# H09R9x.net
KiCad netlist of a schematic drawn in EAGLE
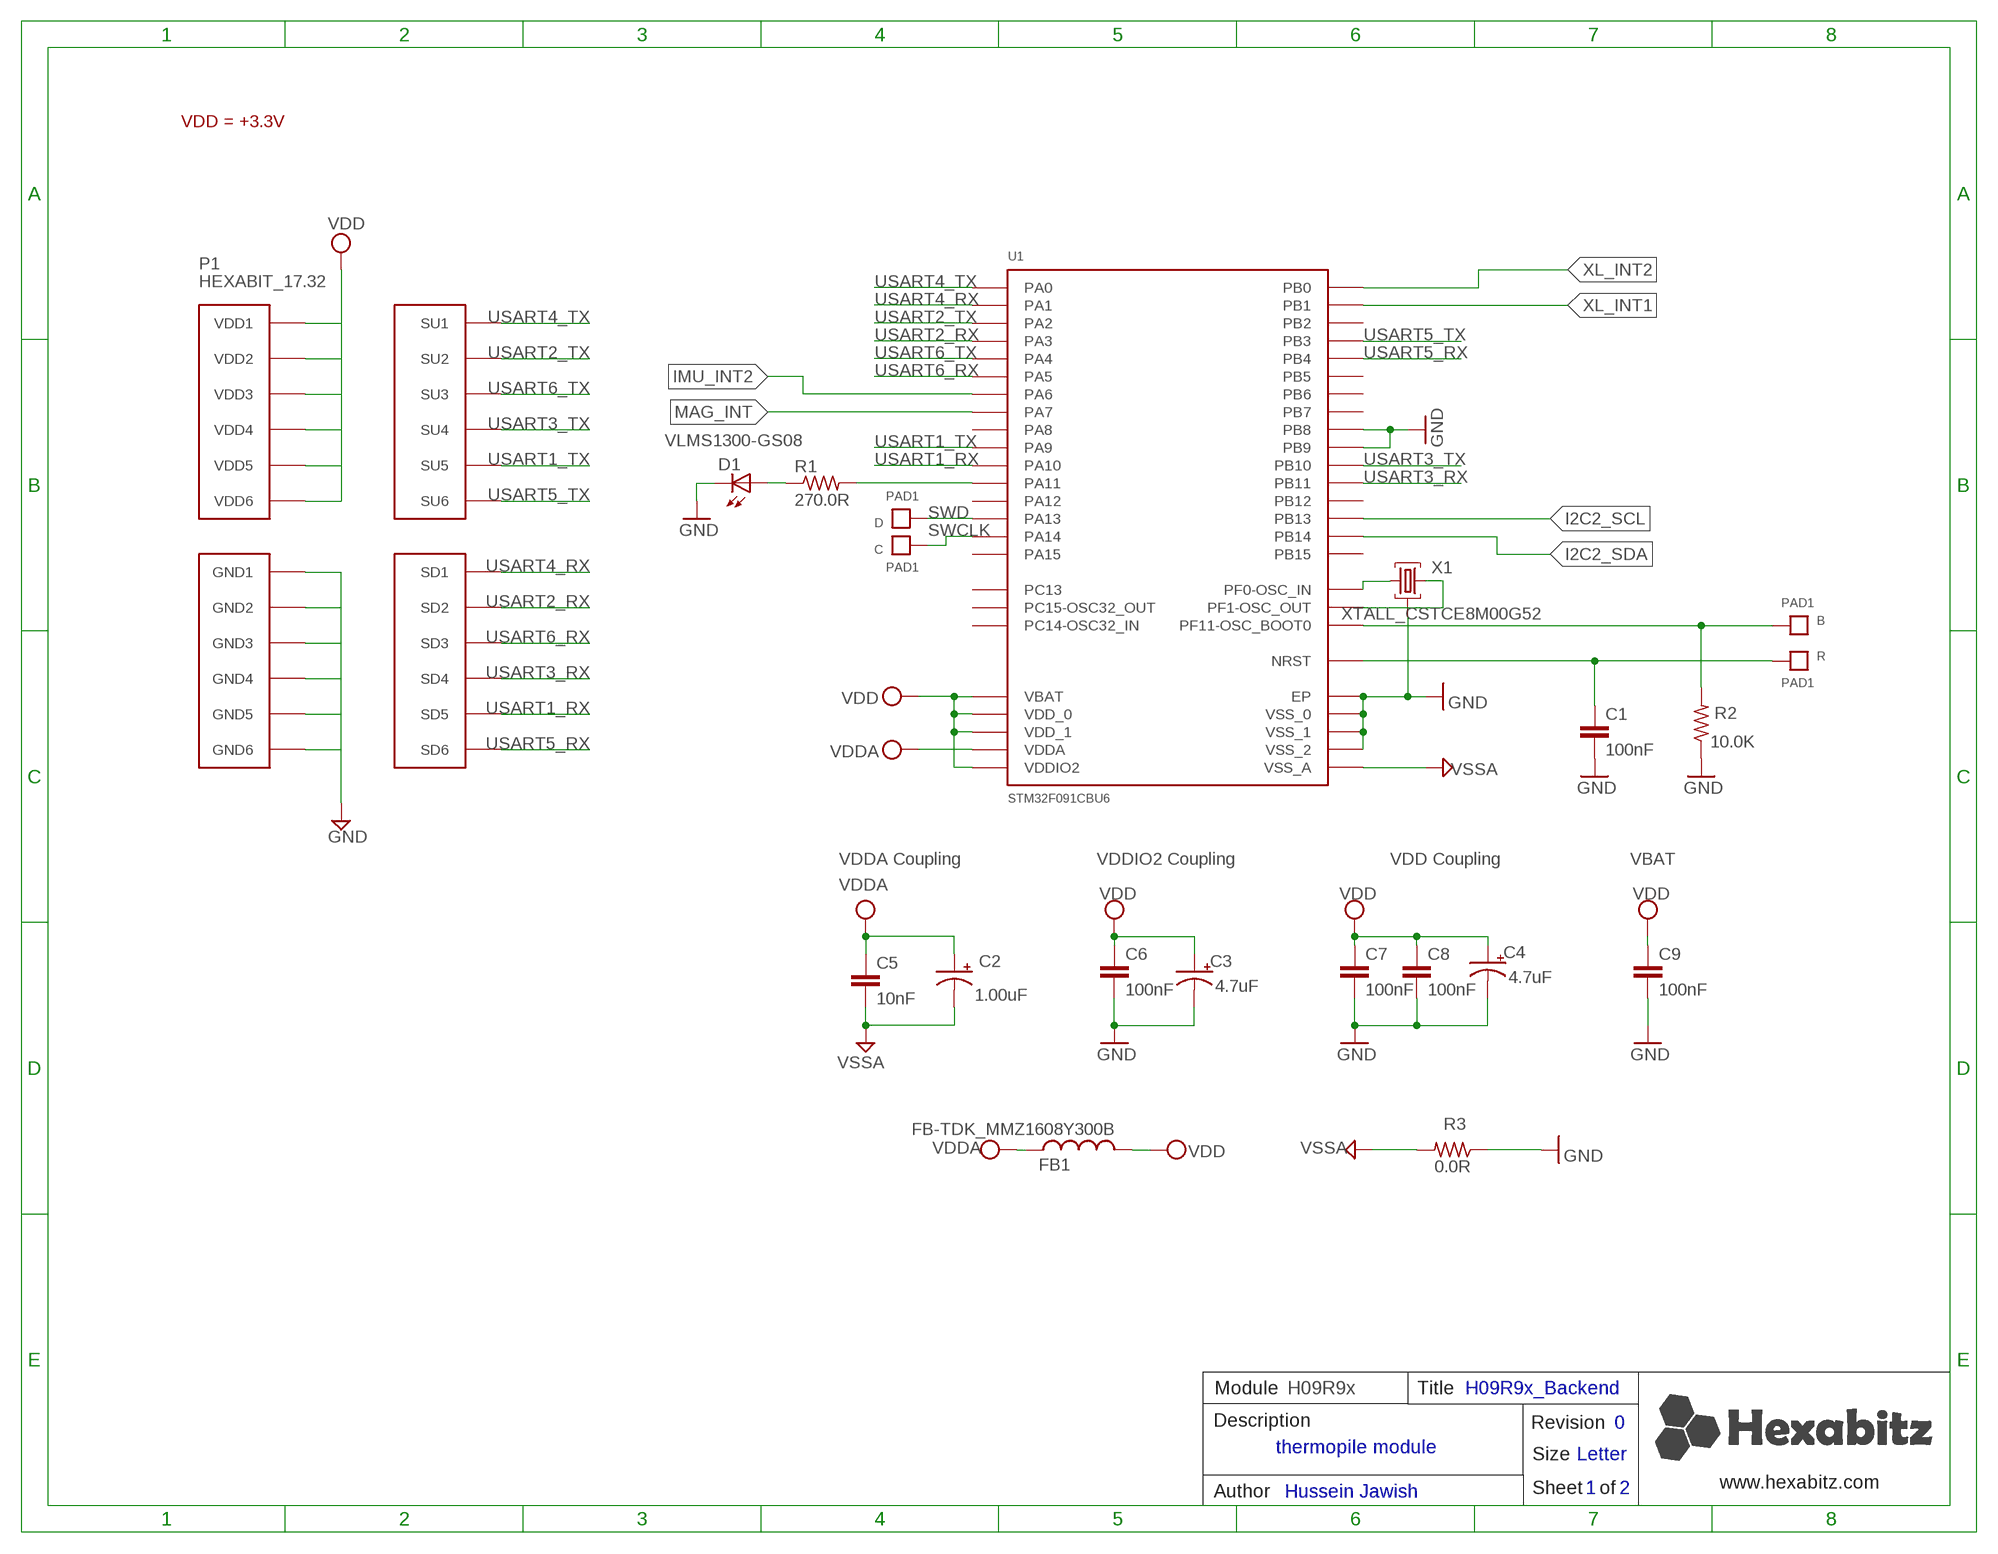
[diagram p0: schematic, sheet 1]
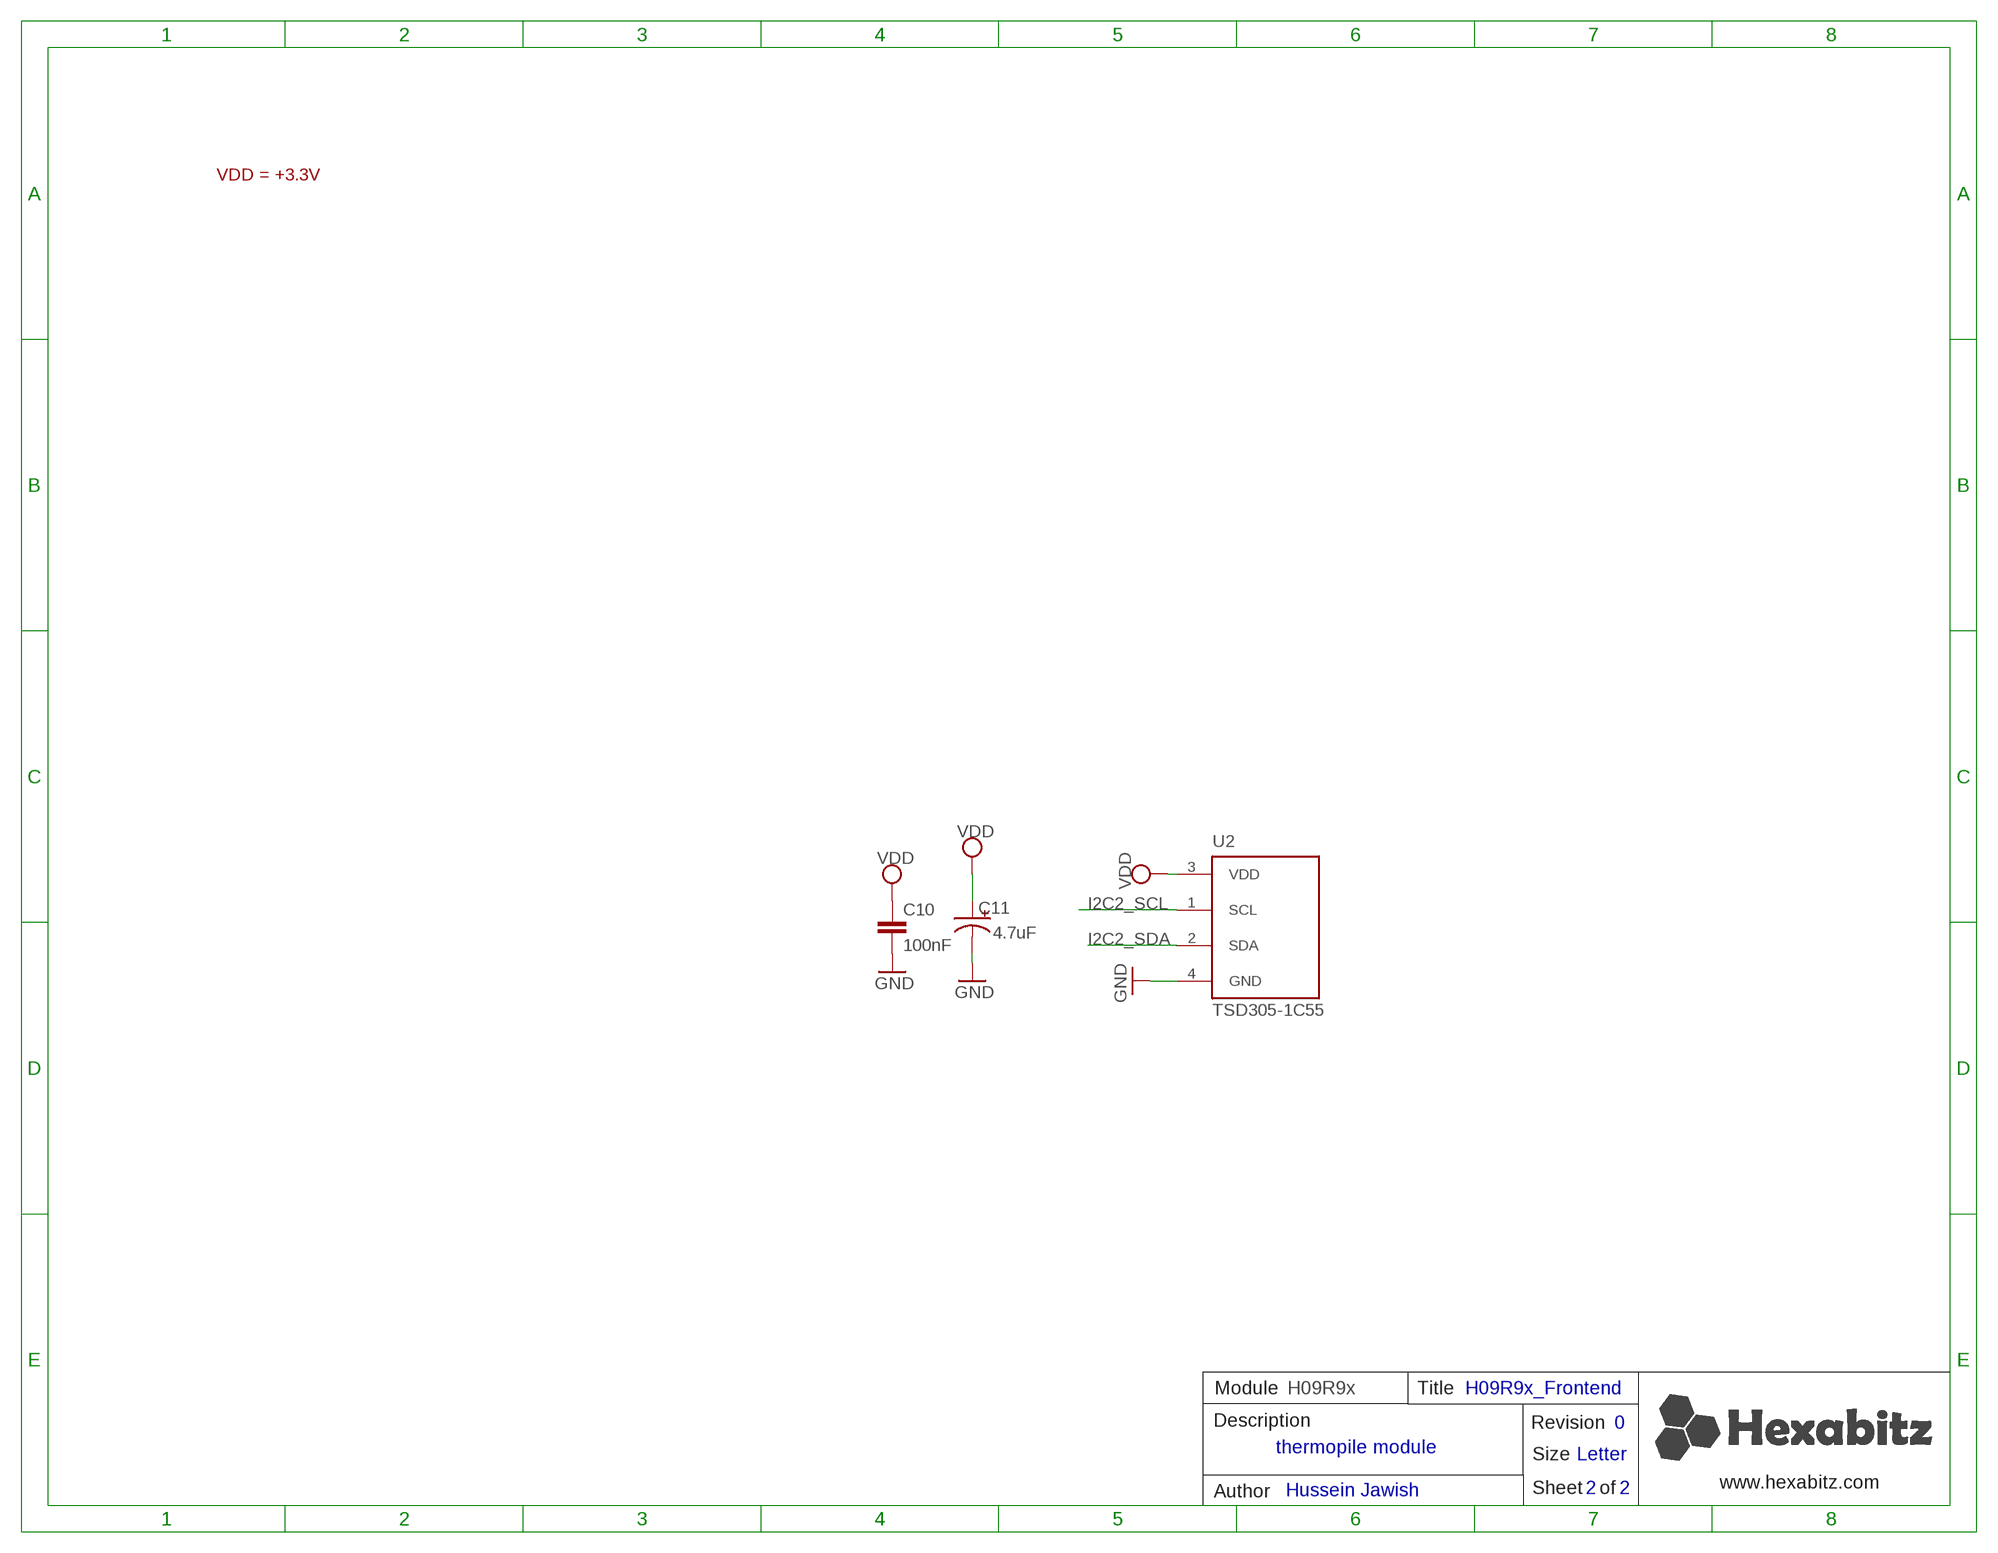
[diagram p1: schematic, sheet 2]

(export (version "E")
  (design (tool "Eeschema 10.0.6"))
  (components
    (comp (ref "B")
      (value "PAD1")
      (footprint "eagle-import:PAD1")
      (libsource (lib "eagle-import") (part "PAD1"))
    )
    (comp (ref "C")
      (value "PAD1")
      (footprint "eagle-import:PAD1")
      (libsource (lib "eagle-import") (part "PAD1"))
    )
    (comp (ref "C1")
      (value "100nF")
      (footprint "eagle-import:C-0603")
      (fields
        (field (name "CAPACITANCE") "100nF")
        (field (name "MFN") "AVX")
        (field (name "MPN") "0603YC104K4T2A")
        (field (name "OCTOPART_URL") "https://octopart.com/0603yc104k4t2a-avx+interconnect+%2F+elco-8120651")
        (field (name "TOLERANCE") "10%")
        (field (name "VOLTAGE_RATING") "16.0 V")
      )
      (libsource (lib "eagle-import") (part "C-0603"))
    )
    (comp (ref "C2")
      (value "1.00uF")
      (footprint "eagle-import:C-0805-POL")
      (fields
        (field (name "CAPACITANCE") "1.00uF")
        (field (name "MFN") "AVX")
        (field (name "MPN") "TAJR105M016RNJ")
        (field (name "OCTOPART_URL") "http://octopart.com/tajr105m016rnj-avx-1188552")
        (field (name "TOLERANCE") "10%")
        (field (name "VOLTAGE_RATING") "16.0 V")
      )
      (libsource (lib "eagle-import") (part "C-0805-POL"))
    )
    (comp (ref "C3")
      (value "4.7uF")
      (footprint "eagle-import:C-0805-POL")
      (fields
        (field (name "CAPACITANCE") "4.7uF")
        (field (name "MFN") "Panasonic")
        (field (name "MPN") "10TPU4R7MSI")
        (field (name "OCTOPART_URL") "https://octopart.com/10tpu4r7msi-panasonic-29487748")
        (field (name "TOLERANCE") "20%")
        (field (name "VOLTAGE_RATING") "10.0 V")
      )
      (libsource (lib "eagle-import") (part "C-0805-POL"))
    )
    (comp (ref "C4")
      (value "4.7uF")
      (footprint "eagle-import:C-0805-POL")
      (fields
        (field (name "CAPACITANCE") "4.7uF")
        (field (name "MFN") "Panasonic")
        (field (name "MPN") "10TPU4R7MSI")
        (field (name "OCTOPART_URL") "https://octopart.com/10tpu4r7msi-panasonic-29487748")
        (field (name "TOLERANCE") "10%")
        (field (name "VOLTAGE_RATING") "10 V")
      )
      (libsource (lib "eagle-import") (part "C-0805-POL"))
    )
    (comp (ref "C5")
      (value "10nF")
      (footprint "eagle-import:C-0603")
      (fields
        (field (name "CAPACITANCE") "10nF")
        (field (name "MFN") "AVX")
        (field (name "MPN") "0603YC103KAT4A")
        (field (name "OCTOPART_URL") "https://octopart.com/0603yc103kat4a-avx+interconnect+%2F+elco-2550362")
        (field (name "TOLERANCE") "10%")
        (field (name "VOLTAGE_RATING") "16.0 V")
      )
      (libsource (lib "eagle-import") (part "C-0603"))
    )
    (comp (ref "C6")
      (value "100nF")
      (footprint "eagle-import:C-0603")
      (fields
        (field (name "CAPACITANCE") "100nF")
        (field (name "MFN") "AVX")
        (field (name "MPN") "0603YC104K4T2A")
        (field (name "OCTOPART_URL") "https://octopart.com/0603yc104k4t2a-avx+interconnect+%2F+elco-8120651")
        (field (name "TOLERANCE") "10%")
        (field (name "VOLTAGE_RATING") "16.0 V")
      )
      (libsource (lib "eagle-import") (part "C-0603"))
    )
    (comp (ref "C7")
      (value "100nF")
      (footprint "eagle-import:C-0603")
      (fields
        (field (name "CAPACITANCE") "100nF")
        (field (name "MFN") "AVX")
        (field (name "MPN") "0603YC104K4T2A")
        (field (name "OCTOPART_URL") "https://octopart.com/0603yc104k4t2a-avx+interconnect+%2F+elco-8120651")
        (field (name "TOLERANCE") "10%")
        (field (name "VOLTAGE_RATING") "16.0 V")
      )
      (libsource (lib "eagle-import") (part "C-0603"))
    )
    (comp (ref "C8")
      (value "100nF")
      (footprint "eagle-import:C-0603")
      (fields
        (field (name "CAPACITANCE") "100nF")
        (field (name "MFN") "AVX")
        (field (name "MPN") "0603YC104K4T2A")
        (field (name "OCTOPART_URL") "https://octopart.com/0603yc104k4t2a-avx+interconnect+%2F+elco-8120651")
        (field (name "TOLERANCE") "10%")
        (field (name "VOLTAGE_RATING") "16.0 V")
      )
      (libsource (lib "eagle-import") (part "C-0603"))
    )
    (comp (ref "C9")
      (value "100nF")
      (footprint "eagle-import:C-0603")
      (fields
        (field (name "CAPACITANCE") "100nF")
        (field (name "MFN") "AVX")
        (field (name "MPN") "0603YC104K4T2A")
        (field (name "OCTOPART_URL") "https://octopart.com/0603yc104k4t2a-avx+interconnect+%2F+elco-8120651")
        (field (name "TOLERANCE") "16.0 V")
        (field (name "VOLTAGE_RATING") "10%")
      )
      (libsource (lib "eagle-import") (part "C-0603"))
    )
    (comp (ref "D")
      (value "PAD1")
      (footprint "eagle-import:PAD1")
      (libsource (lib "eagle-import") (part "PAD1"))
    )
    (comp (ref "D1")
      (value "VLMS1300-GS08")
      (footprint "eagle-import:VLMS1300-GS08")
      (fields
        (field (name "MFN") "Vishay")
        (field (name "MPN") "VLMS1300-GS08")
        (field (name "OCTOPART_URL") "https://octopart.com/vlms1300-gs08-vishay-21709201?r=sp&s=_gcP4_q8T1SC6PJQPTQ9yA")
      )
      (libsource (lib "eagle-import") (part "VLMS1300-GS08"))
    )
    (comp (ref "FB1")
      (value "FB-TDK_MMZ1608Y300B")
      (footprint "eagle-import:FB-TDK_MMZ1608Y300B")
      (fields
        (field (name "MFN") "TDK ")
        (field (name "MPN") "MMZ1608Y300B")
        (field (name "OCTOPART_URL") "https://octopart.com/mmz1608y300b-tdk-368280?r=sp&s=cd9_2ZEqQ9q9UNBuQgHAiA")
      )
      (libsource (lib "eagle-import") (part "FB-TDK_MMZ1608Y300B"))
    )
    (comp (ref "P1")
      (value "HEXABIT_17.32")
      (footprint "eagle-import:HEXABIT_17.32")
      (libsource (lib "eagle-import") (part "HEXABIT_?17.32"))
    )
    (comp (ref "R")
      (value "PAD1")
      (footprint "eagle-import:PAD1")
      (libsource (lib "eagle-import") (part "PAD1"))
    )
    (comp (ref "R1")
      (value "270.0R")
      (footprint "eagle-import:R-0603")
      (fields
        (field (name "MFN") "Panasonic")
        (field (name "MPN") "ERJ-3GEYJ271V")
        (field (name "OCTOPART_URL") "https://octopart.com/erj-3geyj271v-panasonic-55560546")
        (field (name "RESISTANCE") "270.0 Ohm")
        (field (name "TOLERANCE") "5%")
      )
      (libsource (lib "eagle-import") (part "R-0603"))
    )
    (comp (ref "R2")
      (value "10.0K")
      (footprint "eagle-import:R-0603")
      (fields
        (field (name "MFN") "Vishay")
        (field (name "MPN") "CRCW060310K0JNEB")
        (field (name "OCTOPART_URL") "https://octopart.com/crcw060310k0jneb-vishay-46603269")
        (field (name "RESISTANCE") "10.0K Ohm")
        (field (name "TOLERANCE") "5%")
      )
      (libsource (lib "eagle-import") (part "R-0603"))
    )
    (comp (ref "R3")
      (value "0.0R")
      (footprint "eagle-import:R-0603")
      (fields
        (field (name "MFN") "Vishay")
        (field (name "MPN") "CRCW06030000Z0EAHP")
        (field (name "OCTOPART_URL") "https://octopart.com/crcw06030000z0eahp-vishay-44320230")
        (field (name "RESISTANCE") "0.0 Ohm")
      )
      (libsource (lib "eagle-import") (part "R-0603"))
    )
    (comp (ref "U1")
      (value "STM32F091CBU6")
      (footprint "eagle-import:STM32F091CBU6")
      (libsource (lib "eagle-import") (part "STM32F091CBU6"))
    )
    (comp (ref "X1")
      (value "XTALL_CSTCE8M00G52")
      (footprint "eagle-import:XTALL_CSTCE8M00G52")
      (fields (field (name "MPN") "CSTCE8M00G52Z-R0"))
      (libsource (lib "eagle-import") (part "XTALL_CSTCE8M00G52"))
    )
    (comp (ref "C10")
      (value "100nF")
      (footprint "eagle-import:C-0603")
      (fields
        (field (name "CAPACITANCE") "100nF")
        (field (name "MFN") "AVX")
        (field (name "MPN") "0603YC104K4T2A")
        (field (name "OCTOPART_URL") "https://octopart.com/0603yc104k4t2a-avx+interconnect+%2F+elco-8120651")
        (field (name "TOLERANCE") "10%")
        (field (name "VOLTAGE_RATING") "16.0 V")
      )
      (libsource (lib "eagle-import") (part "C-0603"))
    )
    (comp (ref "C11")
      (value "4.7uF")
      (footprint "eagle-import:C-0805-POL")
      (fields
        (field (name "CAPACITANCE") "4.7uF")
        (field (name "MFN") "Panasonic")
        (field (name "MPN") "10TPU4R7MSI")
        (field (name "OCTOPART_URL") "https://octopart.com/10tpu4r7msi-panasonic-29487748")
        (field (name "TOLERANCE") "20%")
        (field (name "VOLTAGE_RATING") "10.0 V")
      )
      (libsource (lib "eagle-import") (part "C-0805-POL"))
    )
    (comp (ref "U2")
      (value "TSD305-1C55")
      (footprint "eagle-import:TEMPERATURESENSOR-TO5")
      (fields (field (name "MPN") "G-TPMO-101"))
      (libsource (lib "eagle-import") (part "TSD305-1C55"))
    )
  )
  (nets
    (net (code "1") (name "GND") (class "Default")
      (node (ref "C1") (pin "2") (pinfunction "2_2") (pintype "passive"))
      (node (ref "C10") (pin "2") (pinfunction "2_2") (pintype "passive"))
      (node (ref "C11") (pin "2") (pinfunction "-_2") (pintype "passive"))
      (node (ref "C3") (pin "2") (pinfunction "-_2") (pintype "passive"))
      (node (ref "C4") (pin "2") (pinfunction "-_2") (pintype "passive"))
      (node (ref "C6") (pin "2") (pinfunction "2_2") (pintype "passive"))
      (node (ref "C7") (pin "2") (pinfunction "2_2") (pintype "passive"))
      (node (ref "C8") (pin "2") (pinfunction "2_2") (pintype "passive"))
      (node (ref "C9") (pin "2") (pinfunction "2_2") (pintype "passive"))
      (node (ref "D1") (pin "C") (pinfunction "C_C") (pintype "passive"))
      (node (ref "P1") (pin "PAD_PD10") (pinfunction "GND4_PAD_PD10") (pintype "power_in"))
      (node (ref "P1") (pin "PAD_PD11") (pinfunction "GND5_PAD_PD11") (pintype "power_in"))
      (node (ref "P1") (pin "PAD_PD12") (pinfunction "GND6_PAD_PD12") (pintype "power_in"))
      (node (ref "P1") (pin "PAD_PD7") (pinfunction "GND1_PAD_PD7") (pintype "power_in"))
      (node (ref "P1") (pin "PAD_PD8") (pinfunction "GND2_PAD_PD8") (pintype "power_in"))
      (node (ref "P1") (pin "PAD_PD9") (pinfunction "GND3_PAD_PD9") (pintype "power_in"))
      (node (ref "R2") (pin "1") (pinfunction "1_1") (pintype "passive"))
      (node (ref "R3") (pin "1") (pinfunction "1_1") (pintype "passive"))
      (node (ref "U1") (pin "EP") (pinfunction "EP_EP") (pintype "power_in"))
      (node (ref "U1") (pin "P$23") (pinfunction "VSS_0_P$23") (pintype "power_in"))
      (node (ref "U1") (pin "P$35") (pinfunction "VSS_1_P$35") (pintype "power_in"))
      (node (ref "U1") (pin "P$45") (pinfunction "PB8_P$45") (pintype "bidirectional"))
      (node (ref "U1") (pin "P$46") (pinfunction "PB9_P$46") (pintype "bidirectional"))
      (node (ref "U1") (pin "P$47") (pinfunction "VSS_2_P$47") (pintype "power_in"))
      (node (ref "U2") (pin "4") (pinfunction "GND_4") (pintype "power_in"))
      (node (ref "X1") (pin "P$2") (pinfunction "2_P$2") (pintype "passive"))
    )
    (net (code "2") (name "I2C2_SCL") (class "Default")
      (node (ref "U1") (pin "P$26") (pinfunction "PB13_P$26") (pintype "bidirectional"))
      (node (ref "U2") (pin "1") (pinfunction "SCL_1") (pintype "bidirectional"))
    )
    (net (code "3") (name "I2C2_SDA") (class "Default")
      (node (ref "U1") (pin "P$27") (pinfunction "PB14_P$27") (pintype "bidirectional"))
      (node (ref "U2") (pin "2") (pinfunction "SDA_2") (pintype "bidirectional"))
    )
    (net (code "4") (name "IMU_INT2") (class "Default")
      (node (ref "U1") (pin "P$16") (pinfunction "PA6_P$16") (pintype "bidirectional"))
    )
    (net (code "5") (name "MAG_INT") (class "Default")
      (node (ref "U1") (pin "P$17") (pinfunction "PA7_P$17") (pintype "bidirectional"))
    )
    (net (code "6") (name "Net-(D1-PadA)") (class "Default")
      (node (ref "D1") (pin "A") (pinfunction "A_A") (pintype "passive"))
      (node (ref "R1") (pin "1") (pinfunction "1_1") (pintype "passive"))
    )
    (net (code "7") (name "Net-(U1-NRST)") (class "Default")
      (node (ref "C1") (pin "1") (pinfunction "1_1") (pintype "passive"))
      (node (ref "R") (pin "P$1") (pinfunction "P$1_P$1") (pintype "passive"))
      (node (ref "R") (pin "P$2") (pinfunction "P$1_P$2") (pintype "passive"))
      (node (ref "U1") (pin "P$7") (pinfunction "NRST_P$7") (pintype "passive"))
    )
    (net (code "8") (name "Net-(U1-PA11)") (class "Default")
      (node (ref "R1") (pin "2") (pinfunction "2_2") (pintype "passive"))
      (node (ref "U1") (pin "P$32") (pinfunction "PA11_P$32") (pintype "bidirectional"))
    )
    (net (code "9") (name "Net-(U1-PF0-OSC_IN)") (class "Default")
      (node (ref "U1") (pin "P$5") (pinfunction "PF0-OSC_IN_P$5") (pintype "bidirectional"))
      (node (ref "X1") (pin "P$1") (pinfunction "1_P$1") (pintype "passive"))
    )
    (net (code "10") (name "Net-(U1-PF1-OSC_OUT)") (class "Default")
      (node (ref "U1") (pin "P$6") (pinfunction "PF1-OSC_OUT_P$6") (pintype "bidirectional"))
      (node (ref "X1") (pin "P$3") (pinfunction "3_P$3") (pintype "passive"))
    )
    (net (code "11") (name "Net-(U1-PF11-OSC_BOOT0)") (class "Default")
      (node (ref "B") (pin "P$1") (pinfunction "P$1_P$1") (pintype "passive"))
      (node (ref "B") (pin "P$2") (pinfunction "P$1_P$2") (pintype "passive"))
      (node (ref "R2") (pin "2") (pinfunction "2_2") (pintype "passive"))
      (node (ref "U1") (pin "P$44") (pinfunction "PF11-OSC_BOOT0_P$44") (pintype "bidirectional"))
    )
    (net (code "12") (name "SWCLK") (class "Default")
      (node (ref "C") (pin "P$1") (pinfunction "P$1_P$1") (pintype "passive"))
      (node (ref "C") (pin "P$2") (pinfunction "P$1_P$2") (pintype "passive"))
      (node (ref "U1") (pin "P$37") (pinfunction "PA14_P$37") (pintype "bidirectional"))
    )
    (net (code "13") (name "SWD") (class "Default")
      (node (ref "D") (pin "P$1") (pinfunction "P$1_P$1") (pintype "passive"))
      (node (ref "D") (pin "P$2") (pinfunction "P$1_P$2") (pintype "passive"))
      (node (ref "U1") (pin "P$34") (pinfunction "PA13_P$34") (pintype "bidirectional"))
    )
    (net (code "14") (name "USART1_RX") (class "Default")
      (node (ref "P1") (pin "PAD_PD5") (pinfunction "SD5_PAD_PD5") (pintype "bidirectional"))
      (node (ref "U1") (pin "P$31") (pinfunction "PA10_P$31") (pintype "bidirectional"))
    )
    (net (code "15") (name "USART1_TX") (class "Default")
      (node (ref "P1") (pin "PAD_PU5") (pinfunction "SU5_PAD_PU5") (pintype "bidirectional"))
      (node (ref "U1") (pin "P$30") (pinfunction "PA9_P$30") (pintype "bidirectional"))
    )
    (net (code "16") (name "USART2_RX") (class "Default")
      (node (ref "P1") (pin "PAD_PD2") (pinfunction "SD2_PAD_PD2") (pintype "bidirectional"))
      (node (ref "U1") (pin "P$13") (pinfunction "PA3_P$13") (pintype "bidirectional"))
    )
    (net (code "17") (name "USART2_TX") (class "Default")
      (node (ref "P1") (pin "PAD_PU2") (pinfunction "SU2_PAD_PU2") (pintype "bidirectional"))
      (node (ref "U1") (pin "P$12") (pinfunction "PA2_P$12") (pintype "bidirectional"))
    )
    (net (code "18") (name "USART3_RX") (class "Default")
      (node (ref "P1") (pin "PAD_PD4") (pinfunction "SD4_PAD_PD4") (pintype "bidirectional"))
      (node (ref "U1") (pin "P$22") (pinfunction "PB11_P$22") (pintype "bidirectional"))
    )
    (net (code "19") (name "USART3_TX") (class "Default")
      (node (ref "P1") (pin "PAD_PU4") (pinfunction "SU4_PAD_PU4") (pintype "bidirectional"))
      (node (ref "U1") (pin "P$21") (pinfunction "PB10_P$21") (pintype "bidirectional"))
    )
    (net (code "20") (name "USART4_RX") (class "Default")
      (node (ref "P1") (pin "PAD_PD1") (pinfunction "SD1_PAD_PD1") (pintype "bidirectional"))
      (node (ref "U1") (pin "P$11") (pinfunction "PA1_P$11") (pintype "bidirectional"))
    )
    (net (code "21") (name "USART4_TX") (class "Default")
      (node (ref "P1") (pin "PAD_PU1") (pinfunction "SU1_PAD_PU1") (pintype "bidirectional"))
      (node (ref "U1") (pin "P$10") (pinfunction "PA0_P$10") (pintype "bidirectional"))
    )
    (net (code "22") (name "USART5_RX") (class "Default")
      (node (ref "P1") (pin "PAD_PD6") (pinfunction "SD6_PAD_PD6") (pintype "bidirectional"))
      (node (ref "U1") (pin "P$40") (pinfunction "PB4_P$40") (pintype "bidirectional"))
    )
    (net (code "23") (name "USART5_TX") (class "Default")
      (node (ref "P1") (pin "PAD_PU6") (pinfunction "SU6_PAD_PU6") (pintype "bidirectional"))
      (node (ref "U1") (pin "P$39") (pinfunction "PB3_P$39") (pintype "bidirectional"))
    )
    (net (code "24") (name "USART6_RX") (class "Default")
      (node (ref "P1") (pin "PAD_PD3") (pinfunction "SD3_PAD_PD3") (pintype "bidirectional"))
      (node (ref "U1") (pin "P$15") (pinfunction "PA5_P$15") (pintype "bidirectional"))
    )
    (net (code "25") (name "USART6_TX") (class "Default")
      (node (ref "P1") (pin "PAD_PU3") (pinfunction "SU3_PAD_PU3") (pintype "bidirectional"))
      (node (ref "U1") (pin "P$14") (pinfunction "PA4_P$14") (pintype "bidirectional"))
    )
    (net (code "26") (name "VDD") (class "Default")
      (node (ref "C10") (pin "1") (pinfunction "1_1") (pintype "passive"))
      (node (ref "C11") (pin "1") (pinfunction "+_1") (pintype "passive"))
      (node (ref "C3") (pin "1") (pinfunction "+_1") (pintype "passive"))
      (node (ref "C4") (pin "1") (pinfunction "+_1") (pintype "passive"))
      (node (ref "C6") (pin "1") (pinfunction "1_1") (pintype "passive"))
      (node (ref "C7") (pin "1") (pinfunction "1_1") (pintype "passive"))
      (node (ref "C8") (pin "1") (pinfunction "1_1") (pintype "passive"))
      (node (ref "C9") (pin "1") (pinfunction "1_1") (pintype "passive"))
      (node (ref "FB1") (pin "2") (pinfunction "2_2") (pintype "passive"))
      (node (ref "P1") (pin "PAD_PU10") (pinfunction "VDD4_PAD_PU10") (pintype "power_in"))
      (node (ref "P1") (pin "PAD_PU11") (pinfunction "VDD5_PAD_PU11") (pintype "power_in"))
      (node (ref "P1") (pin "PAD_PU12") (pinfunction "VDD6_PAD_PU12") (pintype "power_in"))
      (node (ref "P1") (pin "PAD_PU7") (pinfunction "VDD1_PAD_PU7") (pintype "power_in"))
      (node (ref "P1") (pin "PAD_PU8") (pinfunction "VDD2_PAD_PU8") (pintype "power_in"))
      (node (ref "P1") (pin "PAD_PU9") (pinfunction "VDD3_PAD_PU9") (pintype "power_in"))
      (node (ref "U1") (pin "P$1") (pinfunction "VBAT_P$1") (pintype "power_in"))
      (node (ref "U1") (pin "P$24") (pinfunction "VDD_0_P$24") (pintype "power_in"))
      (node (ref "U1") (pin "P$36") (pinfunction "VDDIO2_P$36") (pintype "power_in"))
      (node (ref "U1") (pin "P$48") (pinfunction "VDD_1_P$48") (pintype "power_in"))
      (node (ref "U2") (pin "3") (pinfunction "VDD_3") (pintype "power_in"))
    )
    (net (code "27") (name "VDDA") (class "Default")
      (node (ref "C2") (pin "1") (pinfunction "+_1") (pintype "passive"))
      (node (ref "C5") (pin "1") (pinfunction "1_1") (pintype "passive"))
      (node (ref "FB1") (pin "1") (pinfunction "1_1") (pintype "passive"))
      (node (ref "U1") (pin "P$9") (pinfunction "VDDA_P$9") (pintype "power_in"))
    )
    (net (code "28") (name "VSSA") (class "Default")
      (node (ref "C2") (pin "2") (pinfunction "-_2") (pintype "passive"))
      (node (ref "C5") (pin "2") (pinfunction "2_2") (pintype "passive"))
      (node (ref "R3") (pin "2") (pinfunction "2_2") (pintype "passive"))
      (node (ref "U1") (pin "P$8") (pinfunction "VSS_A_P$8") (pintype "power_in"))
    )
    (net (code "29") (name "XL_INT1") (class "Default")
      (node (ref "U1") (pin "P$19") (pinfunction "PB1_P$19") (pintype "bidirectional"))
    )
    (net (code "30") (name "XL_INT2") (class "Default")
      (node (ref "U1") (pin "P$18") (pinfunction "PB0_P$18") (pintype "bidirectional"))
    )
    (net (code "31") (name "unconnected-(U1-PA8-PadP$29)") (class "Default")
      (node (ref "U1") (pin "P$29") (pinfunction "PA8_P$29") (pintype "bidirectional"))
    )
    (net (code "32") (name "unconnected-(U1-PA12-PadP$33)") (class "Default")
      (node (ref "U1") (pin "P$33") (pinfunction "PA12_P$33") (pintype "bidirectional"))
    )
    (net (code "33") (name "unconnected-(U1-PA15-PadP$38)") (class "Default")
      (node (ref "U1") (pin "P$38") (pinfunction "PA15_P$38") (pintype "bidirectional"))
    )
    (net (code "34") (name "unconnected-(U1-PB2-PadP$20)") (class "Default")
      (node (ref "U1") (pin "P$20") (pinfunction "PB2_P$20") (pintype "bidirectional"))
    )
    (net (code "35") (name "unconnected-(U1-PB5-PadP$41)") (class "Default")
      (node (ref "U1") (pin "P$41") (pinfunction "PB5_P$41") (pintype "bidirectional"))
    )
    (net (code "36") (name "unconnected-(U1-PB6-PadP$42)") (class "Default")
      (node (ref "U1") (pin "P$42") (pinfunction "PB6_P$42") (pintype "bidirectional"))
    )
    (net (code "37") (name "unconnected-(U1-PB7-PadP$43)") (class "Default")
      (node (ref "U1") (pin "P$43") (pinfunction "PB7_P$43") (pintype "bidirectional"))
    )
    (net (code "38") (name "unconnected-(U1-PB12-PadP$25)") (class "Default")
      (node (ref "U1") (pin "P$25") (pinfunction "PB12_P$25") (pintype "bidirectional"))
    )
    (net (code "39") (name "unconnected-(U1-PB15-PadP$28)") (class "Default")
      (node (ref "U1") (pin "P$28") (pinfunction "PB15_P$28") (pintype "bidirectional"))
    )
    (net (code "40") (name "unconnected-(U1-PC13-PadP$2)") (class "Default")
      (node (ref "U1") (pin "P$2") (pinfunction "PC13_P$2") (pintype "bidirectional"))
    )
    (net (code "41") (name "unconnected-(U1-PC14-OSC32_IN-PadP$3)") (class "Default")
      (node (ref "U1") (pin "P$3") (pinfunction "PC14-OSC32_IN_P$3") (pintype "bidirectional"))
    )
    (net (code "42") (name "unconnected-(U1-PC15-OSC32_OUT-PadP$4)") (class "Default")
      (node (ref "U1") (pin "P$4") (pinfunction "PC15-OSC32_OUT_P$4") (pintype "bidirectional"))
    )
  )
)
